# 234_sync_clock_divider.net
KiCad netlist of a schematic drawn in EAGLE
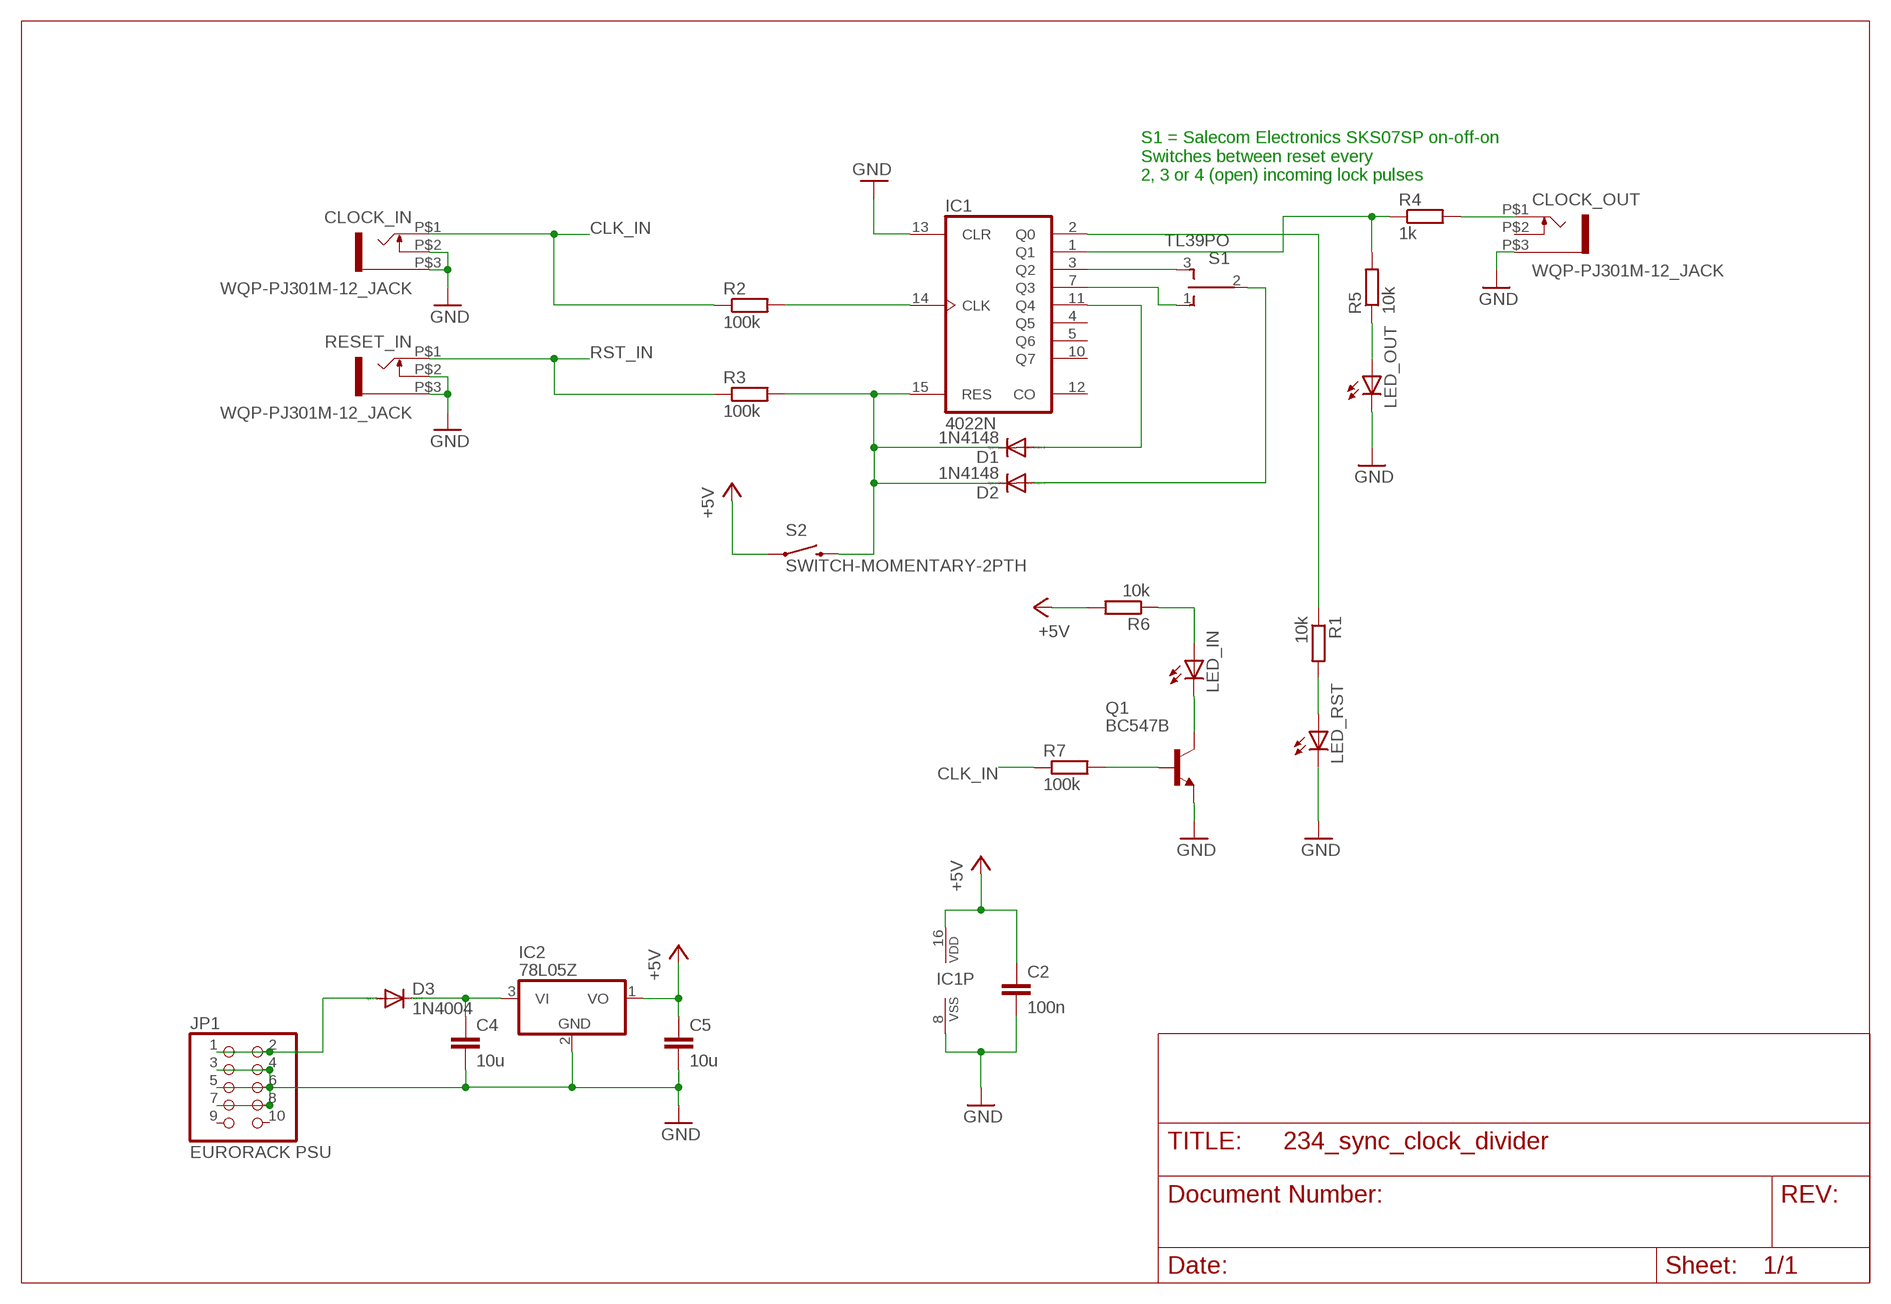
[diagram p0: schematic, sheet 1]

(export (version "E")
  (design (tool "Eeschema 10.0.6"))
  (components
    (comp (ref "C2")
      (value "100n")
      (footprint "eagle-import:C025-025X050")
      (libsource (lib "eagle-import") (part "C-EU025-025X050"))
    )
    (comp (ref "C4")
      (value "10u")
      (footprint "eagle-import:C1206K")
      (libsource (lib "eagle-import") (part "C-EUC1206K"))
    )
    (comp (ref "C5")
      (value "10u")
      (footprint "eagle-import:C1206K")
      (libsource (lib "eagle-import") (part "C-EUC1206K"))
    )
    (comp (ref "CLOCK_IN")
      (value "WQP-PJ301M-12_JACK")
      (footprint "eagle-import:WQP-PJ301M-12_JACK")
      (libsource (lib "eagle-import") (part "WQP-PJ301M-12_JACK"))
    )
    (comp (ref "CLOCK_OUT")
      (value "WQP-PJ301M-12_JACK")
      (footprint "eagle-import:WQP-PJ301M-12_JACK")
      (libsource (lib "eagle-import") (part "WQP-PJ301M-12_JACK"))
    )
    (comp (ref "D1")
      (value "1N4148")
      (footprint "eagle-import:D-2.5")
      (libsource (lib "eagle-import") (part "DIODE-D-2.5"))
    )
    (comp (ref "D2")
      (value "1N4148")
      (footprint "eagle-import:D-2.5")
      (libsource (lib "eagle-import") (part "DIODE-D-2.5"))
    )
    (comp (ref "D3")
      (value "1N4004")
      (footprint "eagle-import:D-2.5")
      (libsource (lib "eagle-import") (part "DIODE-D-2.5"))
    )
    (comp (ref "IC1")
      (value "4022N")
      (footprint "eagle-import:DIL16")
      (libsource (lib "eagle-import") (part "4022N"))
    )
    (comp (ref "IC2")
      (value "78L05Z")
      (footprint "eagle-import:TO92")
      (libsource (lib "eagle-import") (part "78ZL05"))
    )
    (comp (ref "JP1")
      (value "EURORACK PSU")
      (footprint "eagle-import:2X05")
      (libsource (lib "eagle-import") (part "PINHD-2X5"))
    )
    (comp (ref "LED_IN")
      (value "LED3MM")
      (footprint "eagle-import:LED3MM")
      (libsource (lib "eagle-import") (part "LED3MM"))
    )
    (comp (ref "LED_OUT")
      (value "LED3MM")
      (footprint "eagle-import:LED3MM")
      (libsource (lib "eagle-import") (part "LED3MM"))
    )
    (comp (ref "LED_RST")
      (value "LED3MM")
      (footprint "eagle-import:LED3MM")
      (libsource (lib "eagle-import") (part "LED3MM"))
    )
    (comp (ref "Q1")
      (value "BC547B")
      (footprint "eagle-import:TO92")
      (libsource (lib "eagle-import") (part "BC547B"))
    )
    (comp (ref "R1")
      (value "10k")
      (footprint "eagle-import:0204V")
      (libsource (lib "eagle-import") (part "R-EU_0204/2V"))
    )
    (comp (ref "R2")
      (value "100k")
      (footprint "eagle-import:0204V")
      (libsource (lib "eagle-import") (part "R-EU_0204/2V"))
    )
    (comp (ref "R3")
      (value "100k")
      (footprint "eagle-import:0204V")
      (libsource (lib "eagle-import") (part "R-EU_0204/2V"))
    )
    (comp (ref "R4")
      (value "1k")
      (footprint "eagle-import:0204V")
      (libsource (lib "eagle-import") (part "R-EU_0204/2V"))
    )
    (comp (ref "R5")
      (value "10k")
      (footprint "eagle-import:0204V")
      (libsource (lib "eagle-import") (part "R-EU_0204/2V"))
    )
    (comp (ref "R6")
      (value "10k")
      (footprint "eagle-import:0204V")
      (libsource (lib "eagle-import") (part "R-EU_0204/2V"))
    )
    (comp (ref "R7")
      (value "100k")
      (footprint "eagle-import:0204V")
      (libsource (lib "eagle-import") (part "R-EU_0204/2V"))
    )
    (comp (ref "RESET_IN")
      (value "WQP-PJ301M-12_JACK")
      (footprint "eagle-import:WQP-PJ301M-12_JACK")
      (libsource (lib "eagle-import") (part "WQP-PJ301M-12_JACK"))
    )
    (comp (ref "S1")
      (value "TL39PO")
      (footprint "eagle-import:TL3XPO")
      (libsource (lib "eagle-import") (part "TL39PO"))
    )
    (comp (ref "S2")
      (value "SWITCH-MOMENTARY-2PTH")
      (footprint "eagle-import:TACTILE-PTH")
      (libsource (lib "eagle-import") (part "SWITCH-MOMENTARY-2PTH"))
    )
  )
  (nets
    (net (code "1") (name "+5V") (class "Default")
      (node (ref "C2") (pin "1") (pinfunction "1_1") (pintype "passive"))
      (node (ref "C5") (pin "1") (pinfunction "1_1") (pintype "passive"))
      (node (ref "IC1") (pin "16") (pinfunction "VDD_16") (pintype "power_in"))
      (node (ref "IC2") (pin "1") (pinfunction "VO_1") (pintype "passive"))
      (node (ref "R6") (pin "2") (pinfunction "2_2") (pintype "passive"))
      (node (ref "S2") (pin "1") (pinfunction "1_1") (pintype "passive"))
    )
    (net (code "2") (name "/CLK_IN") (class "Default")
      (node (ref "CLOCK_IN") (pin "P$1") (pinfunction "2_P$1") (pintype "passive"))
      (node (ref "R2") (pin "1") (pinfunction "1_1") (pintype "passive"))
      (node (ref "R7") (pin "1") (pinfunction "1_1") (pintype "passive"))
    )
    (net (code "3") (name "/RST_IN") (class "Default")
      (node (ref "R3") (pin "1") (pinfunction "1_1") (pintype "passive"))
      (node (ref "RESET_IN") (pin "P$1") (pinfunction "2_P$1") (pintype "passive"))
    )
    (net (code "4") (name "GND") (class "Default")
      (node (ref "C2") (pin "2") (pinfunction "2_2") (pintype "passive"))
      (node (ref "C4") (pin "2") (pinfunction "2_2") (pintype "passive"))
      (node (ref "C5") (pin "2") (pinfunction "2_2") (pintype "passive"))
      (node (ref "CLOCK_IN") (pin "P$2") (pinfunction "3_P$2") (pintype "passive"))
      (node (ref "CLOCK_IN") (pin "P$3") (pinfunction "1_P$3") (pintype "passive"))
      (node (ref "CLOCK_OUT") (pin "P$3") (pinfunction "1_P$3") (pintype "passive"))
      (node (ref "IC1") (pin "13") (pinfunction "CLR_13") (pintype "input"))
      (node (ref "IC1") (pin "8") (pinfunction "VSS_8") (pintype "power_in"))
      (node (ref "IC2") (pin "2") (pinfunction "GND_2") (pintype "passive"))
      (node (ref "JP1") (pin "3") (pinfunction "3_3") (pintype "passive"))
      (node (ref "JP1") (pin "4") (pinfunction "4_4") (pintype "passive"))
      (node (ref "JP1") (pin "5") (pinfunction "5_5") (pintype "passive"))
      (node (ref "JP1") (pin "6") (pinfunction "6_6") (pintype "passive"))
      (node (ref "JP1") (pin "7") (pinfunction "7_7") (pintype "passive"))
      (node (ref "JP1") (pin "8") (pinfunction "8_8") (pintype "passive"))
      (node (ref "LED_OUT") (pin "K") (pinfunction "C_K") (pintype "passive"))
      (node (ref "LED_RST") (pin "K") (pinfunction "C_K") (pintype "passive"))
      (node (ref "Q1") (pin "1") (pinfunction "E_1") (pintype "passive"))
      (node (ref "RESET_IN") (pin "P$2") (pinfunction "3_P$2") (pintype "passive"))
      (node (ref "RESET_IN") (pin "P$3") (pinfunction "1_P$3") (pintype "passive"))
    )
    (net (code "5") (name "Net-(CLOCK_OUT-2)") (class "Default")
      (node (ref "CLOCK_OUT") (pin "P$1") (pinfunction "2_P$1") (pintype "passive"))
      (node (ref "R4") (pin "2") (pinfunction "2_2") (pintype "passive"))
    )
    (net (code "6") (name "Net-(D3-PadA)") (class "Default")
      (node (ref "D3") (pin "A") (pinfunction "A_A") (pintype "passive"))
      (node (ref "JP1") (pin "1") (pinfunction "1_1") (pintype "passive"))
      (node (ref "JP1") (pin "2") (pinfunction "2_2") (pintype "passive"))
    )
    (net (code "7") (name "Net-(IC1A-CLK)") (class "Default")
      (node (ref "IC1") (pin "14") (pinfunction "CLK_14") (pintype "input"))
      (node (ref "R2") (pin "2") (pinfunction "2_2") (pintype "passive"))
    )
    (net (code "8") (name "Net-(IC1A-Q0)") (class "Default")
      (node (ref "IC1") (pin "2") (pinfunction "Q0_2") (pintype "output"))
      (node (ref "R1") (pin "1") (pinfunction "1_1") (pintype "passive"))
    )
    (net (code "9") (name "Net-(IC1A-Q1)") (class "Default")
      (node (ref "IC1") (pin "1") (pinfunction "Q1_1") (pintype "output"))
      (node (ref "R4") (pin "1") (pinfunction "1_1") (pintype "passive"))
      (node (ref "R5") (pin "2") (pinfunction "2_2") (pintype "passive"))
    )
    (net (code "10") (name "Net-(IC1A-Q2)") (class "Default")
      (node (ref "IC1") (pin "3") (pinfunction "Q2_3") (pintype "output"))
      (node (ref "S1") (pin "3") (pinfunction "S_3") (pintype "passive"))
    )
    (net (code "11") (name "Net-(IC1A-Q3)") (class "Default")
      (node (ref "IC1") (pin "7") (pinfunction "Q3_7") (pintype "output"))
      (node (ref "S1") (pin "1") (pinfunction "O_1") (pintype "passive"))
    )
    (net (code "12") (name "Net-(IC1A-Q4)") (class "Default")
      (node (ref "D1") (pin "A") (pinfunction "A_A") (pintype "passive"))
      (node (ref "IC1") (pin "11") (pinfunction "Q4_11") (pintype "output"))
    )
    (net (code "13") (name "Net-(IC1A-RES)") (class "Default")
      (node (ref "D1") (pin "C") (pinfunction "C_C") (pintype "passive"))
      (node (ref "D2") (pin "C") (pinfunction "C_C") (pintype "passive"))
      (node (ref "IC1") (pin "15") (pinfunction "RES_15") (pintype "input"))
      (node (ref "R3") (pin "2") (pinfunction "2_2") (pintype "passive"))
      (node (ref "S2") (pin "3") (pinfunction "2_3") (pintype "passive"))
    )
    (net (code "14") (name "Net-(IC2-VI)") (class "Default")
      (node (ref "C4") (pin "1") (pinfunction "1_1") (pintype "passive"))
      (node (ref "D3") (pin "C") (pinfunction "C_C") (pintype "passive"))
      (node (ref "IC2") (pin "3") (pinfunction "VI_3") (pintype "input"))
    )
    (net (code "15") (name "Net-(LED_IN-C)") (class "Default")
      (node (ref "LED_IN") (pin "K") (pinfunction "C_K") (pintype "passive"))
      (node (ref "Q1") (pin "3") (pinfunction "C_3") (pintype "passive"))
    )
    (net (code "16") (name "Net-(LED_IN-PadA)") (class "Default")
      (node (ref "LED_IN") (pin "A") (pinfunction "A_A") (pintype "passive"))
      (node (ref "R6") (pin "1") (pinfunction "1_1") (pintype "passive"))
    )
    (net (code "17") (name "Net-(LED_OUT-PadA)") (class "Default")
      (node (ref "LED_OUT") (pin "A") (pinfunction "A_A") (pintype "passive"))
      (node (ref "R5") (pin "1") (pinfunction "1_1") (pintype "passive"))
    )
    (net (code "18") (name "Net-(LED_RST-PadA)") (class "Default")
      (node (ref "LED_RST") (pin "A") (pinfunction "A_A") (pintype "passive"))
      (node (ref "R1") (pin "2") (pinfunction "2_2") (pintype "passive"))
    )
    (net (code "19") (name "Net-(Q1-B)") (class "Default")
      (node (ref "Q1") (pin "2") (pinfunction "B_2") (pintype "passive"))
      (node (ref "R7") (pin "2") (pinfunction "2_2") (pintype "passive"))
    )
    (net (code "20") (name "Net-(S1-P)") (class "Default")
      (node (ref "D2") (pin "A") (pinfunction "A_A") (pintype "passive"))
      (node (ref "S1") (pin "2") (pinfunction "P_2") (pintype "passive"))
    )
    (net (code "21") (name "unconnected-(CLOCK_OUT-3-PadP$2)") (class "Default")
      (node (ref "CLOCK_OUT") (pin "P$2") (pinfunction "3_P$2") (pintype "passive"))
    )
    (net (code "22") (name "unconnected-(IC1A-CO-Pad12)") (class "Default")
      (node (ref "IC1") (pin "12") (pinfunction "CO_12") (pintype "output"))
    )
    (net (code "23") (name "unconnected-(IC1A-Q5-Pad4)") (class "Default")
      (node (ref "IC1") (pin "4") (pinfunction "Q5_4") (pintype "output"))
    )
    (net (code "24") (name "unconnected-(IC1A-Q6-Pad5)") (class "Default")
      (node (ref "IC1") (pin "5") (pinfunction "Q6_5") (pintype "output"))
    )
    (net (code "25") (name "unconnected-(IC1A-Q7-Pad10)") (class "Default")
      (node (ref "IC1") (pin "10") (pinfunction "Q7_10") (pintype "output"))
    )
    (net (code "26") (name "unconnected-(JP1-Pad9)") (class "Default")
      (node (ref "JP1") (pin "9") (pinfunction "9_9") (pintype "passive"))
    )
    (net (code "27") (name "unconnected-(JP1-Pad10)") (class "Default")
      (node (ref "JP1") (pin "10") (pinfunction "10_10") (pintype "passive"))
    )
  )
)
